# fm_transmit_2.net
KiCad netlist of a schematic drawn in EAGLE
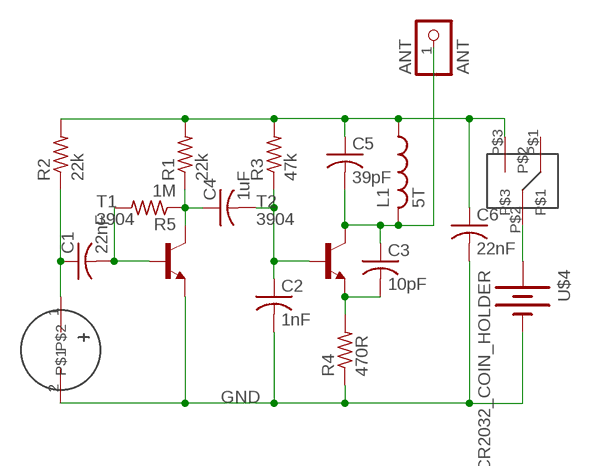
[diagram p0: schematic, sheet 1]

(export (version "E")
  (design (tool "Eeschema 10.0.6"))
  (components
    (comp (ref "ANT")
      (value "ANT")
      (footprint "eagle-import:1X01")
      (libsource (lib "eagle-import") (part "PINHD-1X1"))
    )
    (comp (ref "C1")
      (value "22nF")
      (footprint "eagle-import:C1206")
      (libsource (lib "eagle-import") (part "C-USC1206"))
    )
    (comp (ref "C2")
      (value "1nF")
      (footprint "eagle-import:C1206")
      (libsource (lib "eagle-import") (part "C-USC1206"))
    )
    (comp (ref "C3")
      (value "10pF")
      (footprint "eagle-import:C1206")
      (libsource (lib "eagle-import") (part "C-USC1206"))
    )
    (comp (ref "C4")
      (value "1uF")
      (footprint "eagle-import:C1206")
      (libsource (lib "eagle-import") (part "C-USC1206"))
    )
    (comp (ref "C5")
      (value "39pF")
      (footprint "eagle-import:C1206")
      (libsource (lib "eagle-import") (part "C-USC1206"))
    )
    (comp (ref "C6")
      (value "22nF")
      (footprint "eagle-import:C1206")
      (libsource (lib "eagle-import") (part "C-USC1206"))
    )
    (comp (ref "L1")
      (value "5T")
      (footprint "eagle-import:0207_15")
      (libsource (lib "eagle-import") (part "L-US0207/15"))
    )
    (comp (ref "R1")
      (value "22k")
      (footprint "eagle-import:R1206")
      (libsource (lib "eagle-import") (part "R-US_R1206"))
    )
    (comp (ref "R2")
      (value "22k")
      (footprint "eagle-import:R1206")
      (libsource (lib "eagle-import") (part "R-US_R1206"))
    )
    (comp (ref "R3")
      (value "47k")
      (footprint "eagle-import:R1206")
      (libsource (lib "eagle-import") (part "R-US_R1206"))
    )
    (comp (ref "R4")
      (value "470R")
      (footprint "eagle-import:R1206")
      (libsource (lib "eagle-import") (part "R-US_R1206"))
    )
    (comp (ref "R5")
      (value "1M")
      (footprint "eagle-import:R1206")
      (libsource (lib "eagle-import") (part "R-US_R1206"))
    )
    (comp (ref "T1")
      (value "3904")
      (footprint "eagle-import:SOT23-BEC")
      (libsource (lib "eagle-import") (part "-NPN-SOT23-BECMMBT3904LT1"))
    )
    (comp (ref "T2")
      (value "3904")
      (footprint "eagle-import:SOT23-BEC")
      (libsource (lib "eagle-import") (part "-NPN-SOT23-BECMMBT3904LT1"))
    )
    (comp (ref "U$1")
      (value "SPDT")
      (footprint "eagle-import:SWITCH")
      (libsource (lib "eagle-import") (part "SPDT"))
    )
    (comp (ref "U$2")
      (value "MIC")
      (footprint "eagle-import:MIC")
      (libsource (lib "eagle-import") (part "MIC"))
    )
    (comp (ref "U$4")
      (value "CR2032_COIN_HOLDER")
      (footprint "eagle-import:COIN_HOLDER")
      (libsource (lib "eagle-import") (part "CR2032_COIN_HOLDER"))
    )
  )
  (nets
    (net (code "1") (name "/GND") (class "Default")
      (node (ref "C2") (pin "2") (pinfunction "2_2") (pintype "passive"))
      (node (ref "C6") (pin "2") (pinfunction "2_2") (pintype "passive"))
      (node (ref "R4") (pin "1") (pinfunction "1_1") (pintype "passive"))
      (node (ref "T1") (pin "E") (pinfunction "E_E") (pintype "passive"))
      (node (ref "U$2") (pin "2") (pinfunction "P$2_2") (pintype "bidirectional"))
      (node (ref "U$4") (pin "P$5") (pinfunction "-_P$5") (pintype "power_in"))
    )
    (net (code "2") (name "Net-(ANT-Pad1)") (class "Default")
      (node (ref "ANT") (pin "1") (pinfunction "1_1") (pintype "passive"))
      (node (ref "C3") (pin "1") (pinfunction "1_1") (pintype "passive"))
      (node (ref "C5") (pin "2") (pinfunction "2_2") (pintype "passive"))
      (node (ref "L1") (pin "2") (pinfunction "2_2") (pintype "passive"))
      (node (ref "T2") (pin "C") (pinfunction "C_C") (pintype "passive"))
    )
    (net (code "3") (name "Net-(C1-Pad2)") (class "Default")
      (node (ref "C1") (pin "2") (pinfunction "2_2") (pintype "passive"))
      (node (ref "R5") (pin "2") (pinfunction "2_2") (pintype "passive"))
      (node (ref "T1") (pin "B") (pinfunction "B_B") (pintype "passive"))
    )
    (net (code "4") (name "Net-(C2-Pad1)") (class "Default")
      (node (ref "C2") (pin "1") (pinfunction "1_1") (pintype "passive"))
      (node (ref "C4") (pin "2") (pinfunction "2_2") (pintype "passive"))
      (node (ref "R3") (pin "1") (pinfunction "1_1") (pintype "passive"))
      (node (ref "T2") (pin "B") (pinfunction "B_B") (pintype "passive"))
    )
    (net (code "5") (name "Net-(C3-Pad2)") (class "Default")
      (node (ref "C3") (pin "2") (pinfunction "2_2") (pintype "passive"))
      (node (ref "R4") (pin "2") (pinfunction "2_2") (pintype "passive"))
      (node (ref "T2") (pin "E") (pinfunction "E_E") (pintype "passive"))
    )
    (net (code "6") (name "Net-(C4-Pad1)") (class "Default")
      (node (ref "C4") (pin "1") (pinfunction "1_1") (pintype "passive"))
      (node (ref "R1") (pin "1") (pinfunction "1_1") (pintype "passive"))
      (node (ref "R5") (pin "1") (pinfunction "1_1") (pintype "passive"))
      (node (ref "T1") (pin "C") (pinfunction "C_C") (pintype "passive"))
    )
    (net (code "7") (name "Net-(C5-Pad1)") (class "Default")
      (node (ref "C5") (pin "1") (pinfunction "1_1") (pintype "passive"))
      (node (ref "C6") (pin "1") (pinfunction "1_1") (pintype "passive"))
      (node (ref "L1") (pin "1") (pinfunction "1_1") (pintype "passive"))
      (node (ref "R1") (pin "2") (pinfunction "2_2") (pintype "passive"))
      (node (ref "R2") (pin "2") (pinfunction "2_2") (pintype "passive"))
      (node (ref "R3") (pin "2") (pinfunction "2_2") (pintype "passive"))
      (node (ref "U$1") (pin "P$3") (pinfunction "P$3_P$3") (pintype "bidirectional"))
    )
    (net (code "8") (name "Net-(U$1-PadP$2)") (class "Default")
      (node (ref "U$1") (pin "P$2") (pinfunction "P$2_P$2") (pintype "bidirectional"))
      (node (ref "U$4") (pin "P$1") (pinfunction "+_P$1") (pintype "power_in"))
      (node (ref "U$4") (pin "P$2") (pinfunction "+_P$2") (pintype "power_in"))
      (node (ref "U$4") (pin "P$3") (pinfunction "+_P$3") (pintype "power_in"))
      (node (ref "U$4") (pin "P$4") (pinfunction "+_P$4") (pintype "power_in"))
    )
    (net (code "9") (name "Net-(U$2-P$1)") (class "Default")
      (node (ref "C1") (pin "1") (pinfunction "1_1") (pintype "passive"))
      (node (ref "R2") (pin "1") (pinfunction "1_1") (pintype "passive"))
      (node (ref "U$2") (pin "1") (pinfunction "P$1_1") (pintype "bidirectional"))
    )
    (net (code "10") (name "unconnected-(U$1-PadP$1)") (class "Default")
      (node (ref "U$1") (pin "P$1") (pinfunction "P$1_P$1") (pintype "bidirectional"))
    )
  )
)
